# PGTN_daisy1_controls_5cvin.net
KiCad netlist of a schematic drawn in EAGLE
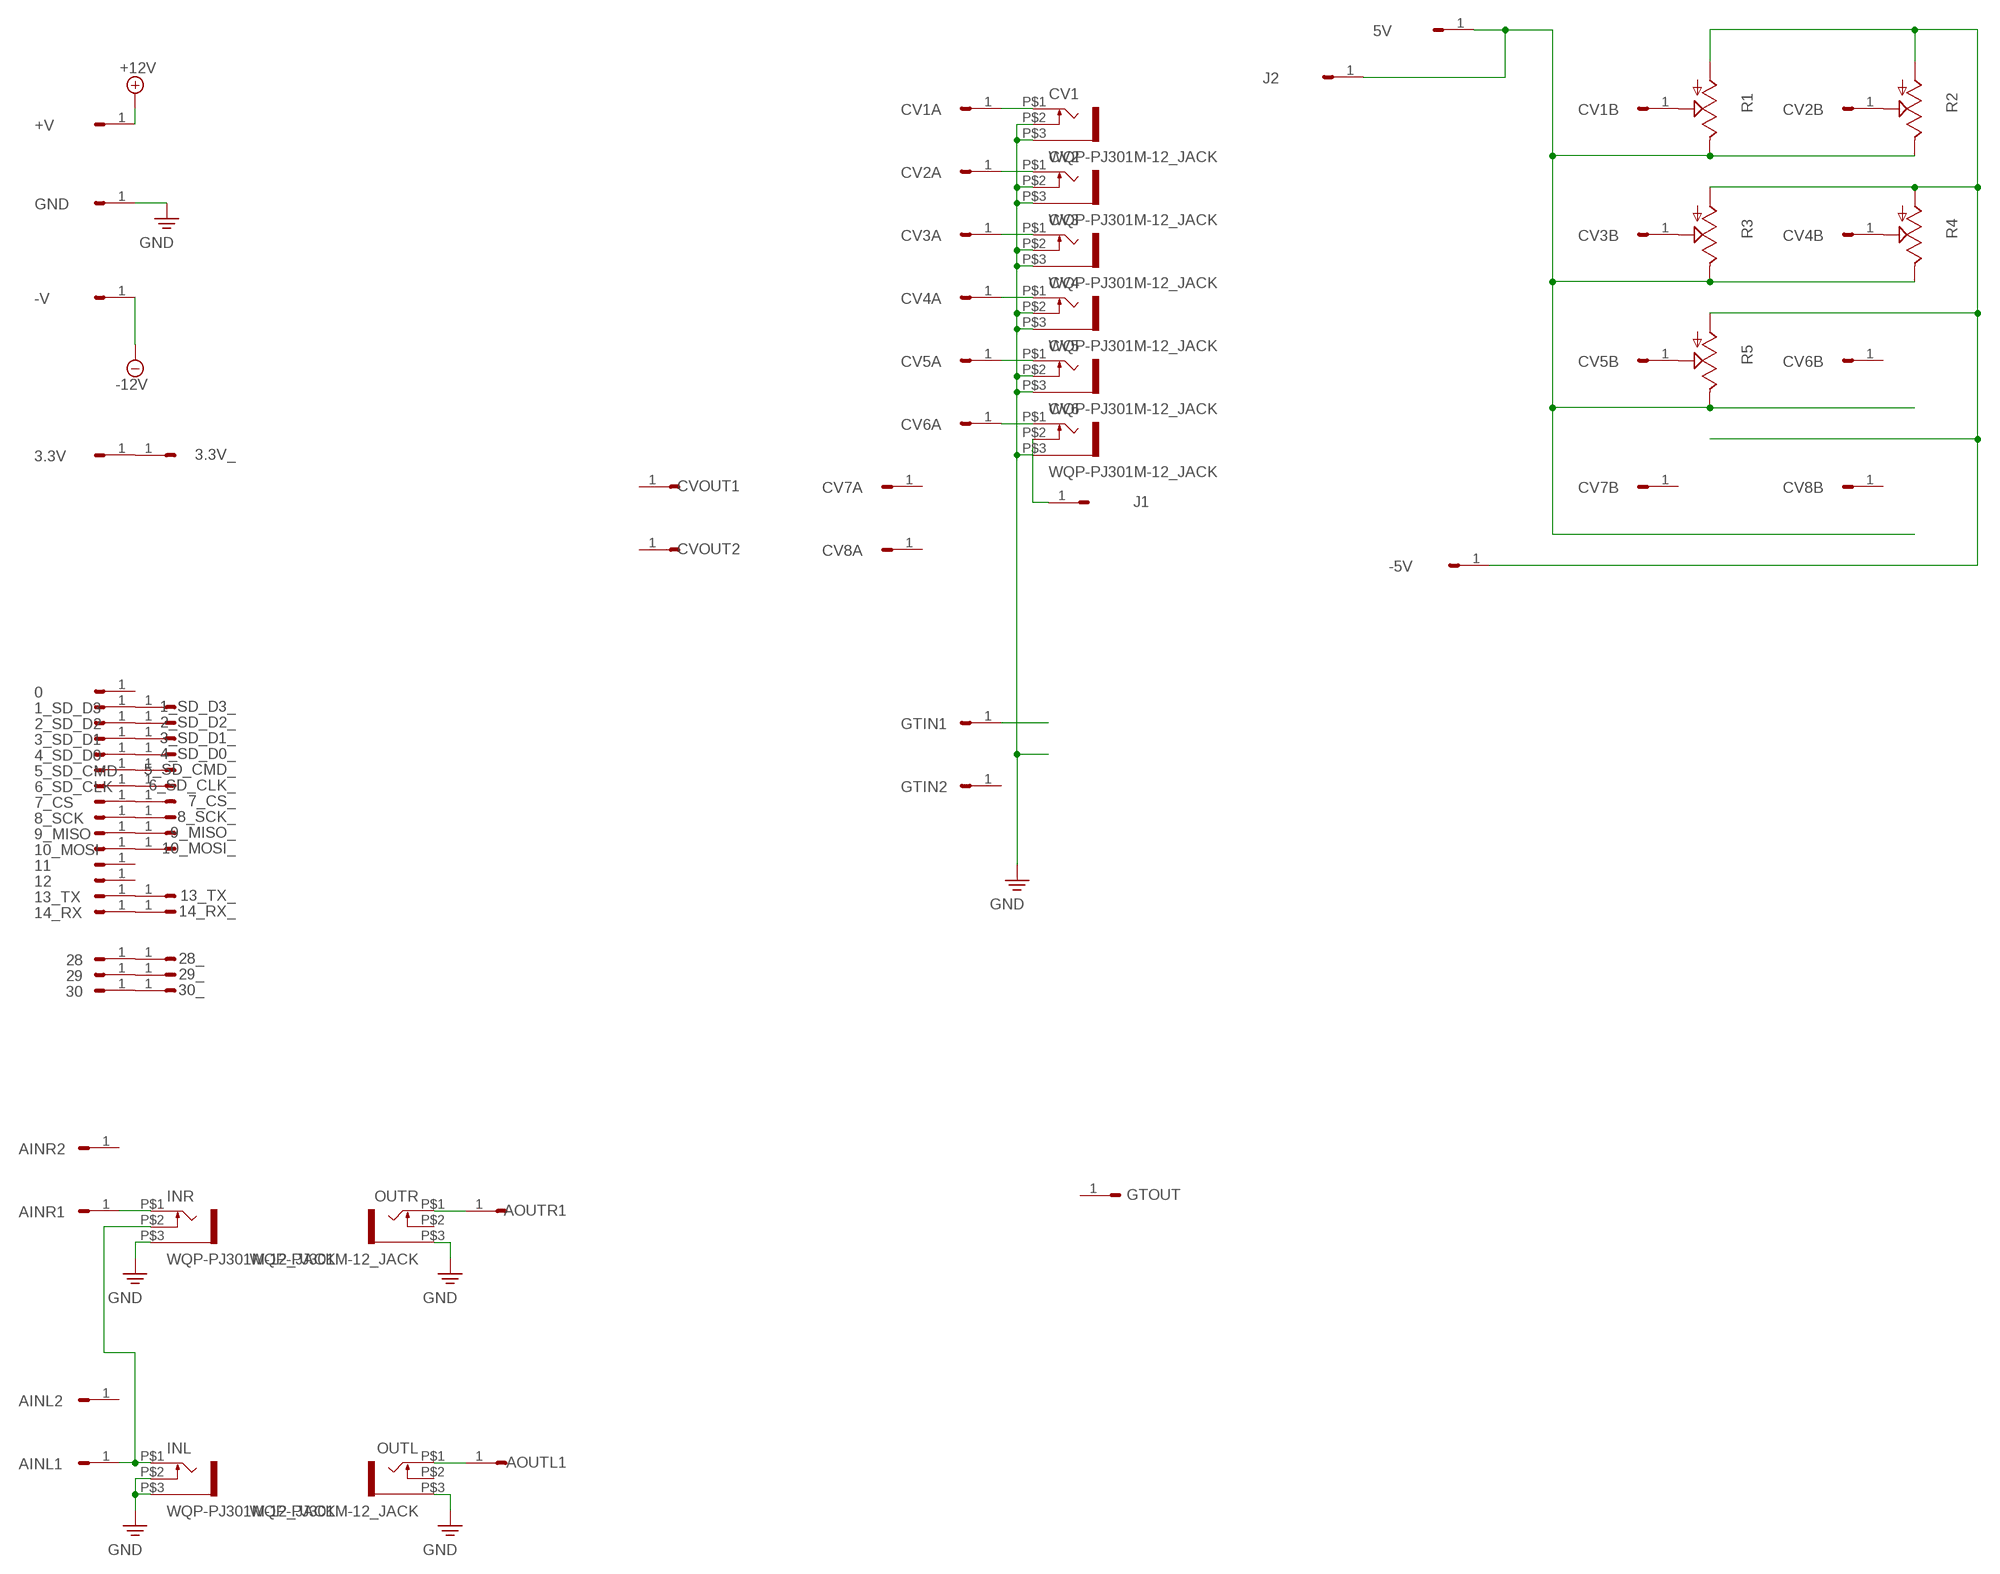
[diagram p0: schematic, sheet 1]

(export (version "E")
  (design (tool "Eeschema 10.0.6"))
  (components
    (comp (ref "+V")
      (value "HEADER/MALE/01")
      (footprint "eagle-import:HEADER_MALE_01")
      (fields (field (name "SPICEPREFIX") "X"))
      (libsource (lib "eagle-import") (part "HEADER/MALE/01"))
    )
    (comp (ref "-5V")
      (value "HEADER/MALE/01")
      (footprint "eagle-import:HEADER_MALE_01")
      (fields (field (name "SPICEPREFIX") "X"))
      (libsource (lib "eagle-import") (part "HEADER/MALE/01"))
    )
    (comp (ref "-V")
      (value "HEADER/MALE/01")
      (footprint "eagle-import:HEADER_MALE_01")
      (fields (field (name "SPICEPREFIX") "X"))
      (libsource (lib "eagle-import") (part "HEADER/MALE/01"))
    )
    (comp (ref "0")
      (value "HEADER/MALE/01")
      (footprint "eagle-import:HEADER_MALE_01")
      (fields (field (name "SPICEPREFIX") "X"))
      (libsource (lib "eagle-import") (part "HEADER/MALE/01"))
    )
    (comp (ref "1_SD_D3")
      (value "HEADER/MALE/01")
      (footprint "eagle-import:HEADER_MALE_01")
      (fields (field (name "SPICEPREFIX") "X"))
      (libsource (lib "eagle-import") (part "HEADER/MALE/01"))
    )
    (comp (ref "1_SD_D3_")
      (value "HEADER/MALE/01")
      (footprint "eagle-import:HEADER_MALE_01")
      (fields (field (name "SPICEPREFIX") "X"))
      (libsource (lib "eagle-import") (part "HEADER/MALE/01"))
    )
    (comp (ref "2_SD_D2")
      (value "HEADER/MALE/01")
      (footprint "eagle-import:HEADER_MALE_01")
      (fields (field (name "SPICEPREFIX") "X"))
      (libsource (lib "eagle-import") (part "HEADER/MALE/01"))
    )
    (comp (ref "2_SD_D2_")
      (value "HEADER/MALE/01")
      (footprint "eagle-import:HEADER_MALE_01")
      (fields (field (name "SPICEPREFIX") "X"))
      (libsource (lib "eagle-import") (part "HEADER/MALE/01"))
    )
    (comp (ref "3.3V")
      (value "HEADER/MALE/01")
      (footprint "eagle-import:HEADER_MALE_01")
      (fields (field (name "SPICEPREFIX") "X"))
      (libsource (lib "eagle-import") (part "HEADER/MALE/01"))
    )
    (comp (ref "3.3V_")
      (value "HEADER/MALE/01")
      (footprint "eagle-import:HEADER_MALE_01")
      (fields (field (name "SPICEPREFIX") "X"))
      (libsource (lib "eagle-import") (part "HEADER/MALE/01"))
    )
    (comp (ref "3_SD_D1")
      (value "HEADER/MALE/01")
      (footprint "eagle-import:HEADER_MALE_01")
      (fields (field (name "SPICEPREFIX") "X"))
      (libsource (lib "eagle-import") (part "HEADER/MALE/01"))
    )
    (comp (ref "3_SD_D1_")
      (value "HEADER/MALE/01")
      (footprint "eagle-import:HEADER_MALE_01")
      (fields (field (name "SPICEPREFIX") "X"))
      (libsource (lib "eagle-import") (part "HEADER/MALE/01"))
    )
    (comp (ref "4_SD_D0")
      (value "HEADER/MALE/01")
      (footprint "eagle-import:HEADER_MALE_01")
      (fields (field (name "SPICEPREFIX") "X"))
      (libsource (lib "eagle-import") (part "HEADER/MALE/01"))
    )
    (comp (ref "4_SD_D0_")
      (value "HEADER/MALE/01")
      (footprint "eagle-import:HEADER_MALE_01")
      (fields (field (name "SPICEPREFIX") "X"))
      (libsource (lib "eagle-import") (part "HEADER/MALE/01"))
    )
    (comp (ref "5V")
      (value "HEADER/MALE/01")
      (footprint "eagle-import:HEADER_MALE_01")
      (fields (field (name "SPICEPREFIX") "X"))
      (libsource (lib "eagle-import") (part "HEADER/MALE/01"))
    )
    (comp (ref "5_SD_CMD")
      (value "HEADER/MALE/01")
      (footprint "eagle-import:HEADER_MALE_01")
      (fields (field (name "SPICEPREFIX") "X"))
      (libsource (lib "eagle-import") (part "HEADER/MALE/01"))
    )
    (comp (ref "5_SD_CMD_")
      (value "HEADER/MALE/01")
      (footprint "eagle-import:HEADER_MALE_01")
      (fields (field (name "SPICEPREFIX") "X"))
      (libsource (lib "eagle-import") (part "HEADER/MALE/01"))
    )
    (comp (ref "6_SD_CLK")
      (value "HEADER/MALE/01")
      (footprint "eagle-import:HEADER_MALE_01")
      (fields (field (name "SPICEPREFIX") "X"))
      (libsource (lib "eagle-import") (part "HEADER/MALE/01"))
    )
    (comp (ref "6_SD_CLK_")
      (value "HEADER/MALE/01")
      (footprint "eagle-import:HEADER_MALE_01")
      (fields (field (name "SPICEPREFIX") "X"))
      (libsource (lib "eagle-import") (part "HEADER/MALE/01"))
    )
    (comp (ref "7_CS")
      (value "HEADER/MALE/01")
      (footprint "eagle-import:HEADER_MALE_01")
      (fields (field (name "SPICEPREFIX") "X"))
      (libsource (lib "eagle-import") (part "HEADER/MALE/01"))
    )
    (comp (ref "7_CS_")
      (value "HEADER/MALE/01")
      (footprint "eagle-import:HEADER_MALE_01")
      (fields (field (name "SPICEPREFIX") "X"))
      (libsource (lib "eagle-import") (part "HEADER/MALE/01"))
    )
    (comp (ref "8_SCK")
      (value "HEADER/MALE/01")
      (footprint "eagle-import:HEADER_MALE_01")
      (fields (field (name "SPICEPREFIX") "X"))
      (libsource (lib "eagle-import") (part "HEADER/MALE/01"))
    )
    (comp (ref "8_SCK_")
      (value "HEADER/MALE/01")
      (footprint "eagle-import:HEADER_MALE_01")
      (fields (field (name "SPICEPREFIX") "X"))
      (libsource (lib "eagle-import") (part "HEADER/MALE/01"))
    )
    (comp (ref "9_MISO")
      (value "HEADER/MALE/01")
      (footprint "eagle-import:HEADER_MALE_01")
      (fields (field (name "SPICEPREFIX") "X"))
      (libsource (lib "eagle-import") (part "HEADER/MALE/01"))
    )
    (comp (ref "9_MISO_")
      (value "HEADER/MALE/01")
      (footprint "eagle-import:HEADER_MALE_01")
      (fields (field (name "SPICEPREFIX") "X"))
      (libsource (lib "eagle-import") (part "HEADER/MALE/01"))
    )
    (comp (ref "10_MOSI")
      (value "HEADER/MALE/01")
      (footprint "eagle-import:HEADER_MALE_01")
      (fields (field (name "SPICEPREFIX") "X"))
      (libsource (lib "eagle-import") (part "HEADER/MALE/01"))
    )
    (comp (ref "10_MOSI_")
      (value "HEADER/MALE/01")
      (footprint "eagle-import:HEADER_MALE_01")
      (fields (field (name "SPICEPREFIX") "X"))
      (libsource (lib "eagle-import") (part "HEADER/MALE/01"))
    )
    (comp (ref "11")
      (value "HEADER/MALE/01")
      (footprint "eagle-import:HEADER_MALE_01")
      (fields (field (name "SPICEPREFIX") "X"))
      (libsource (lib "eagle-import") (part "HEADER/MALE/01"))
    )
    (comp (ref "12")
      (value "HEADER/MALE/01")
      (footprint "eagle-import:HEADER_MALE_01")
      (fields (field (name "SPICEPREFIX") "X"))
      (libsource (lib "eagle-import") (part "HEADER/MALE/01"))
    )
    (comp (ref "13_TX")
      (value "HEADER/MALE/01")
      (footprint "eagle-import:HEADER_MALE_01")
      (fields (field (name "SPICEPREFIX") "X"))
      (libsource (lib "eagle-import") (part "HEADER/MALE/01"))
    )
    (comp (ref "13_TX_")
      (value "HEADER/MALE/01")
      (footprint "eagle-import:HEADER_MALE_01")
      (fields (field (name "SPICEPREFIX") "X"))
      (libsource (lib "eagle-import") (part "HEADER/MALE/01"))
    )
    (comp (ref "14_RX")
      (value "HEADER/MALE/01")
      (footprint "eagle-import:HEADER_MALE_01")
      (fields (field (name "SPICEPREFIX") "X"))
      (libsource (lib "eagle-import") (part "HEADER/MALE/01"))
    )
    (comp (ref "14_RX_")
      (value "HEADER/MALE/01")
      (footprint "eagle-import:HEADER_MALE_01")
      (fields (field (name "SPICEPREFIX") "X"))
      (libsource (lib "eagle-import") (part "HEADER/MALE/01"))
    )
    (comp (ref "28")
      (value "HEADER/MALE/01")
      (footprint "eagle-import:HEADER_MALE_01")
      (fields (field (name "SPICEPREFIX") "X"))
      (libsource (lib "eagle-import") (part "HEADER/MALE/01"))
    )
    (comp (ref "28_")
      (value "HEADER/MALE/01")
      (footprint "eagle-import:HEADER_MALE_01")
      (fields (field (name "SPICEPREFIX") "X"))
      (libsource (lib "eagle-import") (part "HEADER/MALE/01"))
    )
    (comp (ref "29")
      (value "HEADER/MALE/01")
      (footprint "eagle-import:HEADER_MALE_01")
      (fields (field (name "SPICEPREFIX") "X"))
      (libsource (lib "eagle-import") (part "HEADER/MALE/01"))
    )
    (comp (ref "29_")
      (value "HEADER/MALE/01")
      (footprint "eagle-import:HEADER_MALE_01")
      (fields (field (name "SPICEPREFIX") "X"))
      (libsource (lib "eagle-import") (part "HEADER/MALE/01"))
    )
    (comp (ref "30")
      (value "HEADER/MALE/01")
      (footprint "eagle-import:HEADER_MALE_01")
      (fields (field (name "SPICEPREFIX") "X"))
      (libsource (lib "eagle-import") (part "HEADER/MALE/01"))
    )
    (comp (ref "30_")
      (value "HEADER/MALE/01")
      (footprint "eagle-import:HEADER_MALE_01")
      (fields (field (name "SPICEPREFIX") "X"))
      (libsource (lib "eagle-import") (part "HEADER/MALE/01"))
    )
    (comp (ref "AINL1")
      (value "HEADER/MALE/01")
      (footprint "eagle-import:HEADER_MALE_01")
      (fields (field (name "SPICEPREFIX") "X"))
      (libsource (lib "eagle-import") (part "HEADER/MALE/01"))
    )
    (comp (ref "AINL2")
      (value "HEADER/MALE/01")
      (footprint "eagle-import:HEADER_MALE_01")
      (fields (field (name "SPICEPREFIX") "X"))
      (libsource (lib "eagle-import") (part "HEADER/MALE/01"))
    )
    (comp (ref "AINR1")
      (value "HEADER/MALE/01")
      (footprint "eagle-import:HEADER_MALE_01")
      (fields (field (name "SPICEPREFIX") "X"))
      (libsource (lib "eagle-import") (part "HEADER/MALE/01"))
    )
    (comp (ref "AINR2")
      (value "HEADER/MALE/01")
      (footprint "eagle-import:HEADER_MALE_01")
      (fields (field (name "SPICEPREFIX") "X"))
      (libsource (lib "eagle-import") (part "HEADER/MALE/01"))
    )
    (comp (ref "AOUTL1")
      (value "HEADER/MALE/01")
      (footprint "eagle-import:HEADER_MALE_01")
      (fields (field (name "SPICEPREFIX") "X"))
      (libsource (lib "eagle-import") (part "HEADER/MALE/01"))
    )
    (comp (ref "AOUTR1")
      (value "HEADER/MALE/01")
      (footprint "eagle-import:HEADER_MALE_01")
      (fields (field (name "SPICEPREFIX") "X"))
      (libsource (lib "eagle-import") (part "HEADER/MALE/01"))
    )
    (comp (ref "CV1")
      (value "WQP-PJ301M-12_JACK")
      (footprint "eagle-import:WQP-PJ301M-12_JACK")
      (libsource (lib "eagle-import") (part "WQP-PJ301M-12_JACK"))
    )
    (comp (ref "CV1A")
      (value "HEADER/MALE/01")
      (footprint "eagle-import:HEADER_MALE_01")
      (fields (field (name "SPICEPREFIX") "X"))
      (libsource (lib "eagle-import") (part "HEADER/MALE/01"))
    )
    (comp (ref "CV1B")
      (value "HEADER/MALE/01")
      (footprint "eagle-import:HEADER_MALE_01")
      (fields (field (name "SPICEPREFIX") "X"))
      (libsource (lib "eagle-import") (part "HEADER/MALE/01"))
    )
    (comp (ref "CV2")
      (value "WQP-PJ301M-12_JACK")
      (footprint "eagle-import:WQP-PJ301M-12_JACK")
      (libsource (lib "eagle-import") (part "WQP-PJ301M-12_JACK"))
    )
    (comp (ref "CV2A")
      (value "HEADER/MALE/01")
      (footprint "eagle-import:HEADER_MALE_01")
      (fields (field (name "SPICEPREFIX") "X"))
      (libsource (lib "eagle-import") (part "HEADER/MALE/01"))
    )
    (comp (ref "CV2B")
      (value "HEADER/MALE/01")
      (footprint "eagle-import:HEADER_MALE_01")
      (fields (field (name "SPICEPREFIX") "X"))
      (libsource (lib "eagle-import") (part "HEADER/MALE/01"))
    )
    (comp (ref "CV3")
      (value "WQP-PJ301M-12_JACK")
      (footprint "eagle-import:WQP-PJ301M-12_JACK")
      (libsource (lib "eagle-import") (part "WQP-PJ301M-12_JACK"))
    )
    (comp (ref "CV3A")
      (value "HEADER/MALE/01")
      (footprint "eagle-import:HEADER_MALE_01")
      (fields (field (name "SPICEPREFIX") "X"))
      (libsource (lib "eagle-import") (part "HEADER/MALE/01"))
    )
    (comp (ref "CV3B")
      (value "HEADER/MALE/01")
      (footprint "eagle-import:HEADER_MALE_01")
      (fields (field (name "SPICEPREFIX") "X"))
      (libsource (lib "eagle-import") (part "HEADER/MALE/01"))
    )
    (comp (ref "CV4")
      (value "WQP-PJ301M-12_JACK")
      (footprint "eagle-import:WQP-PJ301M-12_JACK")
      (libsource (lib "eagle-import") (part "WQP-PJ301M-12_JACK"))
    )
    (comp (ref "CV4A")
      (value "HEADER/MALE/01")
      (footprint "eagle-import:HEADER_MALE_01")
      (fields (field (name "SPICEPREFIX") "X"))
      (libsource (lib "eagle-import") (part "HEADER/MALE/01"))
    )
    (comp (ref "CV4B")
      (value "HEADER/MALE/01")
      (footprint "eagle-import:HEADER_MALE_01")
      (fields (field (name "SPICEPREFIX") "X"))
      (libsource (lib "eagle-import") (part "HEADER/MALE/01"))
    )
    (comp (ref "CV5")
      (value "WQP-PJ301M-12_JACK")
      (footprint "eagle-import:WQP-PJ301M-12_JACK")
      (libsource (lib "eagle-import") (part "WQP-PJ301M-12_JACK"))
    )
    (comp (ref "CV5A")
      (value "HEADER/MALE/01")
      (footprint "eagle-import:HEADER_MALE_01")
      (fields (field (name "SPICEPREFIX") "X"))
      (libsource (lib "eagle-import") (part "HEADER/MALE/01"))
    )
    (comp (ref "CV5B")
      (value "HEADER/MALE/01")
      (footprint "eagle-import:HEADER_MALE_01")
      (fields (field (name "SPICEPREFIX") "X"))
      (libsource (lib "eagle-import") (part "HEADER/MALE/01"))
    )
    (comp (ref "CV6")
      (value "WQP-PJ301M-12_JACK")
      (footprint "eagle-import:WQP-PJ301M-12_JACK")
      (libsource (lib "eagle-import") (part "WQP-PJ301M-12_JACK"))
    )
    (comp (ref "CV6A")
      (value "HEADER/MALE/01")
      (footprint "eagle-import:HEADER_MALE_01")
      (fields (field (name "SPICEPREFIX") "X"))
      (libsource (lib "eagle-import") (part "HEADER/MALE/01"))
    )
    (comp (ref "CV6B")
      (value "HEADER/MALE/01")
      (footprint "eagle-import:HEADER_MALE_01")
      (fields (field (name "SPICEPREFIX") "X"))
      (libsource (lib "eagle-import") (part "HEADER/MALE/01"))
    )
    (comp (ref "CV7A")
      (value "HEADER/MALE/01")
      (footprint "eagle-import:HEADER_MALE_01")
      (fields (field (name "SPICEPREFIX") "X"))
      (libsource (lib "eagle-import") (part "HEADER/MALE/01"))
    )
    (comp (ref "CV7B")
      (value "HEADER/MALE/01")
      (footprint "eagle-import:HEADER_MALE_01")
      (fields (field (name "SPICEPREFIX") "X"))
      (libsource (lib "eagle-import") (part "HEADER/MALE/01"))
    )
    (comp (ref "CV8A")
      (value "HEADER/MALE/01")
      (footprint "eagle-import:HEADER_MALE_01")
      (fields (field (name "SPICEPREFIX") "X"))
      (libsource (lib "eagle-import") (part "HEADER/MALE/01"))
    )
    (comp (ref "CV8B")
      (value "HEADER/MALE/01")
      (footprint "eagle-import:HEADER_MALE_01")
      (fields (field (name "SPICEPREFIX") "X"))
      (libsource (lib "eagle-import") (part "HEADER/MALE/01"))
    )
    (comp (ref "CVOUT1")
      (value "HEADER/MALE/01")
      (footprint "eagle-import:HEADER_MALE_01")
      (fields (field (name "SPICEPREFIX") "X"))
      (libsource (lib "eagle-import") (part "HEADER/MALE/01"))
    )
    (comp (ref "CVOUT2")
      (value "HEADER/MALE/01")
      (footprint "eagle-import:HEADER_MALE_01")
      (fields (field (name "SPICEPREFIX") "X"))
      (libsource (lib "eagle-import") (part "HEADER/MALE/01"))
    )
    (comp (ref "GND")
      (value "HEADER/MALE/01")
      (footprint "eagle-import:HEADER_MALE_01")
      (fields (field (name "SPICEPREFIX") "X"))
      (libsource (lib "eagle-import") (part "HEADER/MALE/01"))
    )
    (comp (ref "GTIN1")
      (value "HEADER/MALE/01")
      (footprint "eagle-import:HEADER_MALE_01")
      (fields (field (name "SPICEPREFIX") "X"))
      (libsource (lib "eagle-import") (part "HEADER/MALE/01"))
    )
    (comp (ref "GTIN2")
      (value "HEADER/MALE/01")
      (footprint "eagle-import:HEADER_MALE_01")
      (fields (field (name "SPICEPREFIX") "X"))
      (libsource (lib "eagle-import") (part "HEADER/MALE/01"))
    )
    (comp (ref "GTOUT")
      (value "HEADER/MALE/01")
      (footprint "eagle-import:HEADER_MALE_01")
      (fields (field (name "SPICEPREFIX") "X"))
      (libsource (lib "eagle-import") (part "HEADER/MALE/01"))
    )
    (comp (ref "INL")
      (value "WQP-PJ301M-12_JACK")
      (footprint "eagle-import:WQP-PJ301M-12_JACK")
      (libsource (lib "eagle-import") (part "WQP-PJ301M-12_JACK"))
    )
    (comp (ref "INR")
      (value "WQP-PJ301M-12_JACK")
      (footprint "eagle-import:WQP-PJ301M-12_JACK")
      (libsource (lib "eagle-import") (part "WQP-PJ301M-12_JACK"))
    )
    (comp (ref "J1")
      (value "HEADER/MALE/01")
      (footprint "eagle-import:HEADER_MALE_01")
      (fields (field (name "SPICEPREFIX") "X"))
      (libsource (lib "eagle-import") (part "HEADER/MALE/01"))
    )
    (comp (ref "J2")
      (value "HEADER/MALE/01")
      (footprint "eagle-import:HEADER_MALE_01")
      (fields (field (name "SPICEPREFIX") "X"))
      (libsource (lib "eagle-import") (part "HEADER/MALE/01"))
    )
    (comp (ref "OUTL")
      (value "WQP-PJ301M-12_JACK")
      (footprint "eagle-import:WQP-PJ301M-12_JACK")
      (libsource (lib "eagle-import") (part "WQP-PJ301M-12_JACK"))
    )
    (comp (ref "OUTR")
      (value "WQP-PJ301M-12_JACK")
      (footprint "eagle-import:WQP-PJ301M-12_JACK")
      (libsource (lib "eagle-import") (part "WQP-PJ301M-12_JACK"))
    )
    (comp (ref "R1")
      (value "9MM_SNAP-IN_POT_")
      (footprint "eagle-import:9MM_SNAP-IN_POT")
      (libsource (lib "eagle-import") (part "9MM_SNAP-IN_POT_"))
    )
    (comp (ref "R2")
      (value "9MM_SNAP-IN_POT_")
      (footprint "eagle-import:9MM_SNAP-IN_POT")
      (libsource (lib "eagle-import") (part "9MM_SNAP-IN_POT_"))
    )
    (comp (ref "R3")
      (value "9MM_SNAP-IN_POT_")
      (footprint "eagle-import:9MM_SNAP-IN_POT")
      (libsource (lib "eagle-import") (part "9MM_SNAP-IN_POT_"))
    )
    (comp (ref "R4")
      (value "9MM_SNAP-IN_POT_")
      (footprint "eagle-import:9MM_SNAP-IN_POT")
      (libsource (lib "eagle-import") (part "9MM_SNAP-IN_POT_"))
    )
    (comp (ref "R5")
      (value "9MM_SNAP-IN_POT_")
      (footprint "eagle-import:9MM_SNAP-IN_POT")
      (libsource (lib "eagle-import") (part "9MM_SNAP-IN_POT_"))
    )
  )
  (nets
    (net (code "1") (name "+12V") (class "Default")
      (node (ref "+V") (pin "1") (pinfunction "3_1") (pintype "passive"))
    )
    (net (code "2") (name "-12V") (class "Default")
      (node (ref "-V") (pin "1") (pinfunction "3_1") (pintype "passive"))
    )
    (net (code "3") (name "GND") (class "Default")
      (node (ref "CV1") (pin "P$2") (pinfunction "3_P$2") (pintype "passive"))
      (node (ref "CV1") (pin "P$3") (pinfunction "1_P$3") (pintype "passive"))
      (node (ref "CV2") (pin "P$2") (pinfunction "3_P$2") (pintype "passive"))
      (node (ref "CV2") (pin "P$3") (pinfunction "1_P$3") (pintype "passive"))
      (node (ref "CV3") (pin "P$2") (pinfunction "3_P$2") (pintype "passive"))
      (node (ref "CV3") (pin "P$3") (pinfunction "1_P$3") (pintype "passive"))
      (node (ref "CV4") (pin "P$2") (pinfunction "3_P$2") (pintype "passive"))
      (node (ref "CV4") (pin "P$3") (pinfunction "1_P$3") (pintype "passive"))
      (node (ref "CV5") (pin "P$2") (pinfunction "3_P$2") (pintype "passive"))
      (node (ref "CV5") (pin "P$3") (pinfunction "1_P$3") (pintype "passive"))
      (node (ref "CV6") (pin "P$3") (pinfunction "1_P$3") (pintype "passive"))
      (node (ref "GND") (pin "1") (pinfunction "3_1") (pintype "passive"))
      (node (ref "INL") (pin "P$2") (pinfunction "3_P$2") (pintype "passive"))
      (node (ref "INL") (pin "P$3") (pinfunction "1_P$3") (pintype "passive"))
      (node (ref "INR") (pin "P$3") (pinfunction "1_P$3") (pintype "passive"))
      (node (ref "OUTL") (pin "P$3") (pinfunction "1_P$3") (pintype "passive"))
      (node (ref "OUTR") (pin "P$3") (pinfunction "1_P$3") (pintype "passive"))
    )
    (net (code "4") (name "Net-(-5V-3)") (class "Default")
      (node (ref "-5V") (pin "1") (pinfunction "3_1") (pintype "passive"))
      (node (ref "R1") (pin "1") (pinfunction "A_1") (pintype "passive"))
      (node (ref "R2") (pin "1") (pinfunction "A_1") (pintype "passive"))
      (node (ref "R3") (pin "1") (pinfunction "A_1") (pintype "passive"))
      (node (ref "R4") (pin "1") (pinfunction "A_1") (pintype "passive"))
      (node (ref "R5") (pin "1") (pinfunction "A_1") (pintype "passive"))
    )
    (net (code "5") (name "Net-(1_SD_D3-3)") (class "Default")
      (node (ref "1_SD_D3") (pin "1") (pinfunction "3_1") (pintype "passive"))
      (node (ref "1_SD_D3_") (pin "1") (pinfunction "3_1") (pintype "passive"))
    )
    (net (code "6") (name "Net-(2_SD_D2-3)") (class "Default")
      (node (ref "2_SD_D2") (pin "1") (pinfunction "3_1") (pintype "passive"))
      (node (ref "2_SD_D2_") (pin "1") (pinfunction "3_1") (pintype "passive"))
    )
    (net (code "7") (name "Net-(3.3V-3)") (class "Default")
      (node (ref "3.3V") (pin "1") (pinfunction "3_1") (pintype "passive"))
      (node (ref "3.3V_") (pin "1") (pinfunction "3_1") (pintype "passive"))
    )
    (net (code "8") (name "Net-(3_SD_D1-3)") (class "Default")
      (node (ref "3_SD_D1") (pin "1") (pinfunction "3_1") (pintype "passive"))
      (node (ref "3_SD_D1_") (pin "1") (pinfunction "3_1") (pintype "passive"))
    )
    (net (code "9") (name "Net-(4_SD_D0-3)") (class "Default")
      (node (ref "4_SD_D0") (pin "1") (pinfunction "3_1") (pintype "passive"))
      (node (ref "4_SD_D0_") (pin "1") (pinfunction "3_1") (pintype "passive"))
    )
    (net (code "10") (name "Net-(5V-3)") (class "Default")
      (node (ref "5V") (pin "1") (pinfunction "3_1") (pintype "passive"))
      (node (ref "J2") (pin "1") (pinfunction "3_1") (pintype "passive"))
      (node (ref "R1") (pin "3") (pinfunction "E_3") (pintype "passive"))
      (node (ref "R2") (pin "3") (pinfunction "E_3") (pintype "passive"))
      (node (ref "R3") (pin "3") (pinfunction "E_3") (pintype "passive"))
      (node (ref "R4") (pin "3") (pinfunction "E_3") (pintype "passive"))
      (node (ref "R5") (pin "3") (pinfunction "E_3") (pintype "passive"))
    )
    (net (code "11") (name "Net-(5_SD_CMD-3)") (class "Default")
      (node (ref "5_SD_CMD") (pin "1") (pinfunction "3_1") (pintype "passive"))
      (node (ref "5_SD_CMD_") (pin "1") (pinfunction "3_1") (pintype "passive"))
    )
    (net (code "12") (name "Net-(6_SD_CLK-3)") (class "Default")
      (node (ref "6_SD_CLK") (pin "1") (pinfunction "3_1") (pintype "passive"))
      (node (ref "6_SD_CLK_") (pin "1") (pinfunction "3_1") (pintype "passive"))
    )
    (net (code "13") (name "Net-(7_CS-3)") (class "Default")
      (node (ref "7_CS") (pin "1") (pinfunction "3_1") (pintype "passive"))
      (node (ref "7_CS_") (pin "1") (pinfunction "3_1") (pintype "passive"))
    )
    (net (code "14") (name "Net-(8_SCK-3)") (class "Default")
      (node (ref "8_SCK") (pin "1") (pinfunction "3_1") (pintype "passive"))
      (node (ref "8_SCK_") (pin "1") (pinfunction "3_1") (pintype "passive"))
    )
    (net (code "15") (name "Net-(9_MISO-3)") (class "Default")
      (node (ref "9_MISO") (pin "1") (pinfunction "3_1") (pintype "passive"))
      (node (ref "9_MISO_") (pin "1") (pinfunction "3_1") (pintype "passive"))
    )
    (net (code "16") (name "Net-(10_MOSI-3)") (class "Default")
      (node (ref "10_MOSI") (pin "1") (pinfunction "3_1") (pintype "passive"))
      (node (ref "10_MOSI_") (pin "1") (pinfunction "3_1") (pintype "passive"))
    )
    (net (code "17") (name "Net-(13_TX-3)") (class "Default")
      (node (ref "13_TX") (pin "1") (pinfunction "3_1") (pintype "passive"))
      (node (ref "13_TX_") (pin "1") (pinfunction "3_1") (pintype "passive"))
    )
    (net (code "18") (name "Net-(14_RX-3)") (class "Default")
      (node (ref "14_RX") (pin "1") (pinfunction "3_1") (pintype "passive"))
      (node (ref "14_RX_") (pin "1") (pinfunction "3_1") (pintype "passive"))
    )
    (net (code "19") (name "Net-(28-3)") (class "Default")
      (node (ref "28") (pin "1") (pinfunction "3_1") (pintype "passive"))
      (node (ref "28_") (pin "1") (pinfunction "3_1") (pintype "passive"))
    )
    (net (code "20") (name "Net-(29-3)") (class "Default")
      (node (ref "29") (pin "1") (pinfunction "3_1") (pintype "passive"))
      (node (ref "29_") (pin "1") (pinfunction "3_1") (pintype "passive"))
    )
    (net (code "21") (name "Net-(30-3)") (class "Default")
      (node (ref "30") (pin "1") (pinfunction "3_1") (pintype "passive"))
      (node (ref "30_") (pin "1") (pinfunction "3_1") (pintype "passive"))
    )
    (net (code "22") (name "Net-(AINL1-3)") (class "Default")
      (node (ref "AINL1") (pin "1") (pinfunction "3_1") (pintype "passive"))
      (node (ref "INL") (pin "P$1") (pinfunction "2_P$1") (pintype "passive"))
      (node (ref "INR") (pin "P$2") (pinfunction "3_P$2") (pintype "passive"))
    )
    (net (code "23") (name "Net-(AINR1-3)") (class "Default")
      (node (ref "AINR1") (pin "1") (pinfunction "3_1") (pintype "passive"))
      (node (ref "INR") (pin "P$1") (pinfunction "2_P$1") (pintype "passive"))
    )
    (net (code "24") (name "Net-(AOUTL1-3)") (class "Default")
      (node (ref "AOUTL1") (pin "1") (pinfunction "3_1") (pintype "passive"))
      (node (ref "OUTL") (pin "P$1") (pinfunction "2_P$1") (pintype "passive"))
    )
    (net (code "25") (name "Net-(AOUTR1-3)") (class "Default")
      (node (ref "AOUTR1") (pin "1") (pinfunction "3_1") (pintype "passive"))
      (node (ref "OUTR") (pin "P$1") (pinfunction "2_P$1") (pintype "passive"))
    )
    (net (code "26") (name "Net-(CV1-2)") (class "Default")
      (node (ref "CV1") (pin "P$1") (pinfunction "2_P$1") (pintype "passive"))
      (node (ref "CV1A") (pin "1") (pinfunction "3_1") (pintype "passive"))
    )
    (net (code "27") (name "Net-(CV1B-3)") (class "Default")
      (node (ref "CV1B") (pin "1") (pinfunction "3_1") (pintype "passive"))
      (node (ref "R1") (pin "2") (pinfunction "S_2") (pintype "passive"))
    )
    (net (code "28") (name "Net-(CV2-2)") (class "Default")
      (node (ref "CV2") (pin "P$1") (pinfunction "2_P$1") (pintype "passive"))
      (node (ref "CV2A") (pin "1") (pinfunction "3_1") (pintype "passive"))
    )
    (net (code "29") (name "Net-(CV2B-3)") (class "Default")
      (node (ref "CV2B") (pin "1") (pinfunction "3_1") (pintype "passive"))
      (node (ref "R2") (pin "2") (pinfunction "S_2") (pintype "passive"))
    )
    (net (code "30") (name "Net-(CV3-2)") (class "Default")
      (node (ref "CV3") (pin "P$1") (pinfunction "2_P$1") (pintype "passive"))
      (node (ref "CV3A") (pin "1") (pinfunction "3_1") (pintype "passive"))
    )
    (net (code "31") (name "Net-(CV3B-3)") (class "Default")
      (node (ref "CV3B") (pin "1") (pinfunction "3_1") (pintype "passive"))
      (node (ref "R3") (pin "2") (pinfunction "S_2") (pintype "passive"))
    )
    (net (code "32") (name "Net-(CV4-2)") (class "Default")
      (node (ref "CV4") (pin "P$1") (pinfunction "2_P$1") (pintype "passive"))
      (node (ref "CV4A") (pin "1") (pinfunction "3_1") (pintype "passive"))
    )
    (net (code "33") (name "Net-(CV4B-3)") (class "Default")
      (node (ref "CV4B") (pin "1") (pinfunction "3_1") (pintype "passive"))
      (node (ref "R4") (pin "2") (pinfunction "S_2") (pintype "passive"))
    )
    (net (code "34") (name "Net-(CV5-2)") (class "Default")
      (node (ref "CV5") (pin "P$1") (pinfunction "2_P$1") (pintype "passive"))
      (node (ref "CV5A") (pin "1") (pinfunction "3_1") (pintype "passive"))
    )
    (net (code "35") (name "Net-(CV5B-3)") (class "Default")
      (node (ref "CV5B") (pin "1") (pinfunction "3_1") (pintype "passive"))
      (node (ref "R5") (pin "2") (pinfunction "S_2") (pintype "passive"))
    )
    (net (code "36") (name "Net-(CV6-2)") (class "Default")
      (node (ref "CV6") (pin "P$1") (pinfunction "2_P$1") (pintype "passive"))
      (node (ref "CV6A") (pin "1") (pinfunction "3_1") (pintype "passive"))
    )
    (net (code "37") (name "Net-(CV6-3)") (class "Default")
      (node (ref "CV6") (pin "P$2") (pinfunction "3_P$2") (pintype "passive"))
      (node (ref "J1") (pin "1") (pinfunction "3_1") (pintype "passive"))
    )
    (net (code "38") (name "unconnected-(0-3-Pad1)") (class "Default")
      (node (ref "0") (pin "1") (pinfunction "3_1") (pintype "passive"))
    )
    (net (code "39") (name "unconnected-(11-3-Pad1)") (class "Default")
      (node (ref "11") (pin "1") (pinfunction "3_1") (pintype "passive"))
    )
    (net (code "40") (name "unconnected-(12-3-Pad1)") (class "Default")
      (node (ref "12") (pin "1") (pinfunction "3_1") (pintype "passive"))
    )
    (net (code "41") (name "unconnected-(AINL2-3-Pad1)") (class "Default")
      (node (ref "AINL2") (pin "1") (pinfunction "3_1") (pintype "passive"))
    )
    (net (code "42") (name "unconnected-(AINR2-3-Pad1)") (class "Default")
      (node (ref "AINR2") (pin "1") (pinfunction "3_1") (pintype "passive"))
    )
    (net (code "43") (name "unconnected-(CV6B-3-Pad1)") (class "Default")
      (node (ref "CV6B") (pin "1") (pinfunction "3_1") (pintype "passive"))
    )
    (net (code "44") (name "unconnected-(CV7A-3-Pad1)") (class "Default")
      (node (ref "CV7A") (pin "1") (pinfunction "3_1") (pintype "passive"))
    )
    (net (code "45") (name "unconnected-(CV7B-3-Pad1)") (class "Default")
      (node (ref "CV7B") (pin "1") (pinfunction "3_1") (pintype "passive"))
    )
    (net (code "46") (name "unconnected-(CV8A-3-Pad1)") (class "Default")
      (node (ref "CV8A") (pin "1") (pinfunction "3_1") (pintype "passive"))
    )
    (net (code "47") (name "unconnected-(CV8B-3-Pad1)") (class "Default")
      (node (ref "CV8B") (pin "1") (pinfunction "3_1") (pintype "passive"))
    )
    (net (code "48") (name "unconnected-(CVOUT1-3-Pad1)") (class "Default")
      (node (ref "CVOUT1") (pin "1") (pinfunction "3_1") (pintype "passive"))
    )
    (net (code "49") (name "unconnected-(CVOUT2-3-Pad1)") (class "Default")
      (node (ref "CVOUT2") (pin "1") (pinfunction "3_1") (pintype "passive"))
    )
    (net (code "50") (name "unconnected-(GTIN1-3-Pad1)") (class "Default")
      (node (ref "GTIN1") (pin "1") (pinfunction "3_1") (pintype "passive"))
    )
    (net (code "51") (name "unconnected-(GTIN2-3-Pad1)") (class "Default")
      (node (ref "GTIN2") (pin "1") (pinfunction "3_1") (pintype "passive"))
    )
    (net (code "52") (name "unconnected-(GTOUT-3-Pad1)") (class "Default")
      (node (ref "GTOUT") (pin "1") (pinfunction "3_1") (pintype "passive"))
    )
    (net (code "53") (name "unconnected-(OUTL-3-PadP$2)") (class "Default")
      (node (ref "OUTL") (pin "P$2") (pinfunction "3_P$2") (pintype "passive"))
    )
    (net (code "54") (name "unconnected-(OUTR-3-PadP$2)") (class "Default")
      (node (ref "OUTR") (pin "P$2") (pinfunction "3_P$2") (pintype "passive"))
    )
  )
)
